# B171B.net
KiCad netlist of a schematic drawn in EAGLE
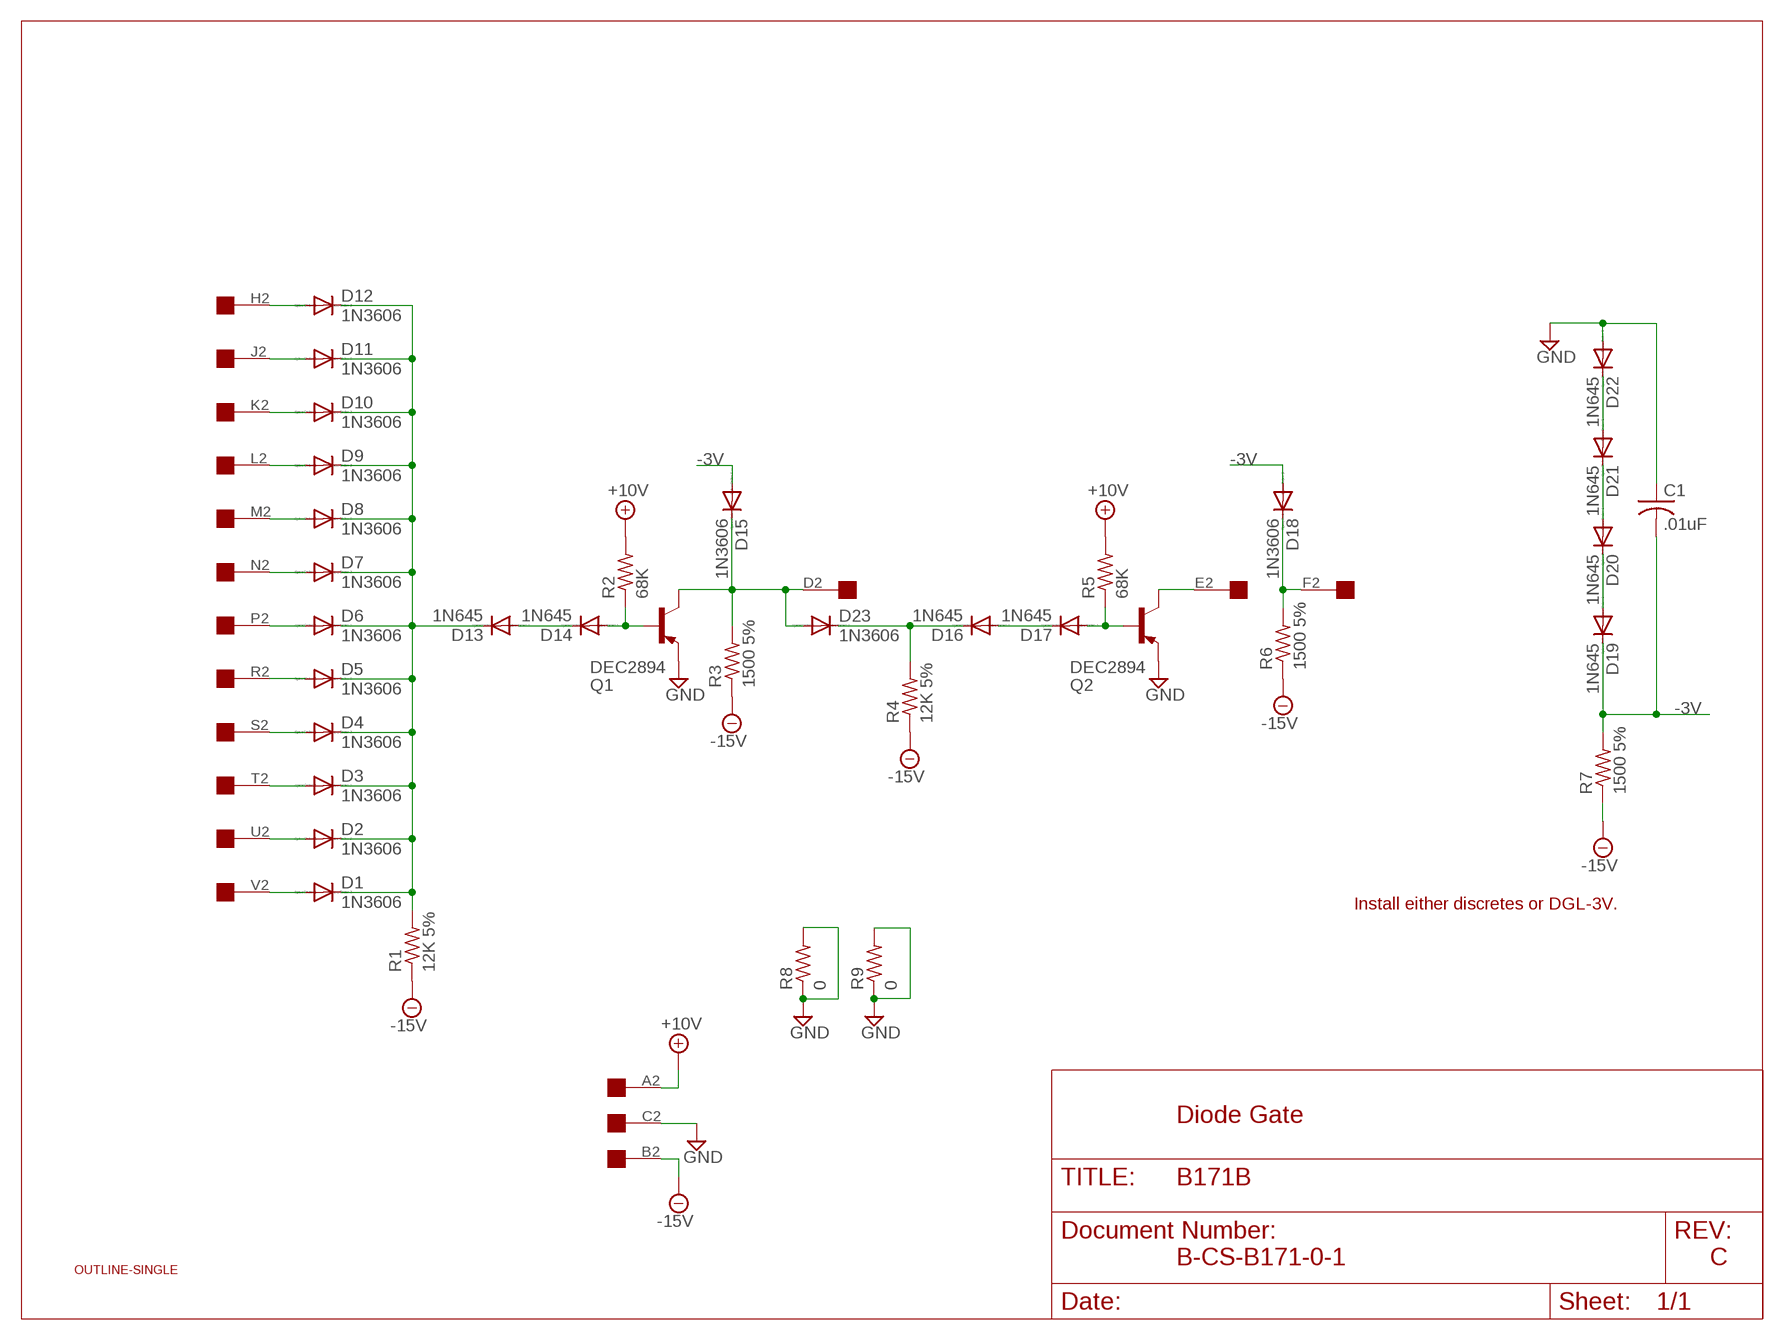
[diagram p0: schematic, sheet 1]

(export (version "E")
  (design (tool "Eeschema 10.0.6"))
  (components
    (comp (ref "C1")
      (value ".01uF")
      (footprint "eagle-import:C063-025X075")
      (libsource (lib "eagle-import") (part "C-US"))
    )
    (comp (ref "D1")
      (value "1N3606")
      (footprint "eagle-import:DO35-10")
      (libsource (lib "eagle-import") (part "DIODE-DO35-10"))
    )
    (comp (ref "D2")
      (value "1N3606")
      (footprint "eagle-import:DO35-10")
      (libsource (lib "eagle-import") (part "DIODE-DO35-10"))
    )
    (comp (ref "D3")
      (value "1N3606")
      (footprint "eagle-import:DO35-10")
      (libsource (lib "eagle-import") (part "DIODE-DO35-10"))
    )
    (comp (ref "D4")
      (value "1N3606")
      (footprint "eagle-import:DO35-10")
      (libsource (lib "eagle-import") (part "DIODE-DO35-10"))
    )
    (comp (ref "D5")
      (value "1N3606")
      (footprint "eagle-import:DO35-10")
      (libsource (lib "eagle-import") (part "DIODE-DO35-10"))
    )
    (comp (ref "D6")
      (value "1N3606")
      (footprint "eagle-import:DO35-10")
      (libsource (lib "eagle-import") (part "DIODE-DO35-10"))
    )
    (comp (ref "D7")
      (value "1N3606")
      (footprint "eagle-import:DO35-10")
      (libsource (lib "eagle-import") (part "DIODE-DO35-10"))
    )
    (comp (ref "D8")
      (value "1N3606")
      (footprint "eagle-import:DO35-10")
      (libsource (lib "eagle-import") (part "DIODE-DO35-10"))
    )
    (comp (ref "D9")
      (value "1N3606")
      (footprint "eagle-import:DO35-10")
      (libsource (lib "eagle-import") (part "DIODE-DO35-10"))
    )
    (comp (ref "D10")
      (value "1N3606")
      (footprint "eagle-import:DO35-10")
      (libsource (lib "eagle-import") (part "DIODE-DO35-10"))
    )
    (comp (ref "D11")
      (value "1N3606")
      (footprint "eagle-import:DO35-10")
      (libsource (lib "eagle-import") (part "DIODE-DO35-10"))
    )
    (comp (ref "D12")
      (value "1N3606")
      (footprint "eagle-import:DO35-10")
      (libsource (lib "eagle-import") (part "DIODE-DO35-10"))
    )
    (comp (ref "D13")
      (value "1N645")
      (footprint "eagle-import:DO35-10")
      (libsource (lib "eagle-import") (part "DIODE-DO35-10"))
    )
    (comp (ref "D14")
      (value "1N645")
      (footprint "eagle-import:DO35-10")
      (libsource (lib "eagle-import") (part "DIODE-DO35-10"))
    )
    (comp (ref "D15")
      (value "1N3606")
      (footprint "eagle-import:DO35-10")
      (libsource (lib "eagle-import") (part "DIODE-DO35-10"))
    )
    (comp (ref "D16")
      (value "1N645")
      (footprint "eagle-import:DO35-10")
      (libsource (lib "eagle-import") (part "DIODE-DO35-10"))
    )
    (comp (ref "D17")
      (value "1N645")
      (footprint "eagle-import:DO35-10")
      (libsource (lib "eagle-import") (part "DIODE-DO35-10"))
    )
    (comp (ref "D18")
      (value "1N3606")
      (footprint "eagle-import:DO35-10")
      (libsource (lib "eagle-import") (part "DIODE-DO35-10"))
    )
    (comp (ref "D19")
      (value "1N645")
      (footprint "eagle-import:DO35-10")
      (libsource (lib "eagle-import") (part "DIODE-DO35-10"))
    )
    (comp (ref "D20")
      (value "1N645")
      (footprint "eagle-import:DO35-10")
      (libsource (lib "eagle-import") (part "DIODE-DO35-10"))
    )
    (comp (ref "D21")
      (value "1N645")
      (footprint "eagle-import:DO35-10")
      (libsource (lib "eagle-import") (part "DIODE-DO35-10"))
    )
    (comp (ref "D22")
      (value "1N645")
      (footprint "eagle-import:DO35-10")
      (libsource (lib "eagle-import") (part "DIODE-DO35-10"))
    )
    (comp (ref "D23")
      (value "1N3606")
      (footprint "eagle-import:DO35-10")
      (libsource (lib "eagle-import") (part "DIODE-DO35-10"))
    )
    (comp (ref "Q1")
      (value "DEC2894")
      (footprint "eagle-import:TO5")
      (libsource (lib "eagle-import") (part "-PNP-TO5"))
    )
    (comp (ref "Q2")
      (value "DEC2894")
      (footprint "eagle-import:TO5")
      (libsource (lib "eagle-import") (part "-PNP-TO5"))
    )
    (comp (ref "R1")
      (value "12K 5%")
      (footprint "eagle-import:0207_10")
      (libsource (lib "eagle-import") (part "R-US_0207/10"))
    )
    (comp (ref "R2")
      (value "68K")
      (footprint "eagle-import:0207_10")
      (libsource (lib "eagle-import") (part "R-US_0207/10"))
    )
    (comp (ref "R3")
      (value "1500 5%")
      (footprint "eagle-import:0207_10")
      (libsource (lib "eagle-import") (part "R-US_0207/10"))
    )
    (comp (ref "R4")
      (value "12K 5%")
      (footprint "eagle-import:0207_10")
      (libsource (lib "eagle-import") (part "R-US_0207/10"))
    )
    (comp (ref "R5")
      (value "68K")
      (footprint "eagle-import:0207_10")
      (libsource (lib "eagle-import") (part "R-US_0207/10"))
    )
    (comp (ref "R6")
      (value "1500 5%")
      (footprint "eagle-import:0207_10")
      (libsource (lib "eagle-import") (part "R-US_0207/10"))
    )
    (comp (ref "R7")
      (value "1500 5%")
      (footprint "eagle-import:0207_10")
      (libsource (lib "eagle-import") (part "R-US_0207/10"))
    )
    (comp (ref "R8")
      (value "0")
      (footprint "eagle-import:0207_10")
      (libsource (lib "eagle-import") (part "R-US_0207/10"))
    )
    (comp (ref "R9")
      (value "0")
      (footprint "eagle-import:0207_10")
      (libsource (lib "eagle-import") (part "R-US_0207/10"))
    )
    (comp (ref "U$1")
      (value "OUTLINE-SINGLE")
      (footprint "eagle-import:SINGLE")
      (libsource (lib "eagle-import") (part "OUTLINE-SINGLE"))
    )
    (comp (ref "U$2")
      (value "EDGE-1")
      (footprint "eagle-import:EDGE-CON1")
      (libsource (lib "eagle-import") (part "EDGE-1"))
    )
  )
  (nets
    (net (code "1") (name "+10V") (class "Default")
      (node (ref "R2") (pin "2") (pinfunction "2_2") (pintype "passive"))
      (node (ref "R5") (pin "2") (pinfunction "2_2") (pintype "passive"))
      (node (ref "U$2") (pin "A2") (pinfunction "1_A2") (pintype "bidirectional"))
    )
    (net (code "2") (name "-15V") (class "Default")
      (node (ref "R1") (pin "1") (pinfunction "1_1") (pintype "passive"))
      (node (ref "R3") (pin "1") (pinfunction "1_1") (pintype "passive"))
      (node (ref "R4") (pin "1") (pinfunction "1_1") (pintype "passive"))
      (node (ref "R6") (pin "1") (pinfunction "1_1") (pintype "passive"))
      (node (ref "R7") (pin "1") (pinfunction "1_1") (pintype "passive"))
      (node (ref "U$2") (pin "B2") (pinfunction "1_B2") (pintype "bidirectional"))
    )
    (net (code "3") (name "/-3V") (class "Default")
      (node (ref "C1") (pin "2") (pinfunction "2_2") (pintype "passive"))
      (node (ref "D15") (pin "A") (pinfunction "A_A") (pintype "passive"))
      (node (ref "D18") (pin "A") (pinfunction "A_A") (pintype "passive"))
      (node (ref "D19") (pin "C") (pinfunction "C_C") (pintype "passive"))
      (node (ref "R7") (pin "2") (pinfunction "2_2") (pintype "passive"))
    )
    (net (code "4") (name "GND") (class "Default")
      (node (ref "C1") (pin "1") (pinfunction "1_1") (pintype "passive"))
      (node (ref "D22") (pin "A") (pinfunction "A_A") (pintype "passive"))
      (node (ref "Q1") (pin "1") (pinfunction "E_1") (pintype "passive"))
      (node (ref "Q2") (pin "1") (pinfunction "E_1") (pintype "passive"))
      (node (ref "R8") (pin "1") (pinfunction "1_1") (pintype "passive"))
      (node (ref "R8") (pin "2") (pinfunction "2_2") (pintype "passive"))
      (node (ref "R9") (pin "1") (pinfunction "1_1") (pintype "passive"))
      (node (ref "R9") (pin "2") (pinfunction "2_2") (pintype "passive"))
      (node (ref "U$2") (pin "C2") (pinfunction "1_C2") (pintype "bidirectional"))
    )
    (net (code "5") (name "Net-(D1-PadC)") (class "Default")
      (node (ref "D1") (pin "C") (pinfunction "C_C") (pintype "passive"))
      (node (ref "D10") (pin "C") (pinfunction "C_C") (pintype "passive"))
      (node (ref "D11") (pin "C") (pinfunction "C_C") (pintype "passive"))
      (node (ref "D12") (pin "C") (pinfunction "C_C") (pintype "passive"))
      (node (ref "D13") (pin "C") (pinfunction "C_C") (pintype "passive"))
      (node (ref "D2") (pin "C") (pinfunction "C_C") (pintype "passive"))
      (node (ref "D3") (pin "C") (pinfunction "C_C") (pintype "passive"))
      (node (ref "D4") (pin "C") (pinfunction "C_C") (pintype "passive"))
      (node (ref "D5") (pin "C") (pinfunction "C_C") (pintype "passive"))
      (node (ref "D6") (pin "C") (pinfunction "C_C") (pintype "passive"))
      (node (ref "D7") (pin "C") (pinfunction "C_C") (pintype "passive"))
      (node (ref "D8") (pin "C") (pinfunction "C_C") (pintype "passive"))
      (node (ref "D9") (pin "C") (pinfunction "C_C") (pintype "passive"))
      (node (ref "R1") (pin "2") (pinfunction "2_2") (pintype "passive"))
    )
    (net (code "6") (name "Net-(D13-PadA)") (class "Default")
      (node (ref "D13") (pin "A") (pinfunction "A_A") (pintype "passive"))
      (node (ref "D14") (pin "C") (pinfunction "C_C") (pintype "passive"))
    )
    (net (code "7") (name "Net-(D16-PadA)") (class "Default")
      (node (ref "D16") (pin "A") (pinfunction "A_A") (pintype "passive"))
      (node (ref "D17") (pin "C") (pinfunction "C_C") (pintype "passive"))
    )
    (net (code "8") (name "Net-(D16-PadC)") (class "Default")
      (node (ref "D16") (pin "C") (pinfunction "C_C") (pintype "passive"))
      (node (ref "D23") (pin "C") (pinfunction "C_C") (pintype "passive"))
      (node (ref "R4") (pin "2") (pinfunction "2_2") (pintype "passive"))
    )
    (net (code "9") (name "Net-(D19-PadA)") (class "Default")
      (node (ref "D19") (pin "A") (pinfunction "A_A") (pintype "passive"))
      (node (ref "D20") (pin "C") (pinfunction "C_C") (pintype "passive"))
    )
    (net (code "10") (name "Net-(D20-PadA)") (class "Default")
      (node (ref "D20") (pin "A") (pinfunction "A_A") (pintype "passive"))
      (node (ref "D21") (pin "C") (pinfunction "C_C") (pintype "passive"))
    )
    (net (code "11") (name "Net-(D21-PadA)") (class "Default")
      (node (ref "D21") (pin "A") (pinfunction "A_A") (pintype "passive"))
      (node (ref "D22") (pin "C") (pinfunction "C_C") (pintype "passive"))
    )
    (net (code "12") (name "Net-(Q1-B)") (class "Default")
      (node (ref "D14") (pin "A") (pinfunction "A_A") (pintype "passive"))
      (node (ref "Q1") (pin "2") (pinfunction "B_2") (pintype "passive"))
      (node (ref "R2") (pin "1") (pinfunction "1_1") (pintype "passive"))
    )
    (net (code "13") (name "Net-(Q1-C)") (class "Default")
      (node (ref "D15") (pin "C") (pinfunction "C_C") (pintype "passive"))
      (node (ref "D23") (pin "A") (pinfunction "A_A") (pintype "passive"))
      (node (ref "Q1") (pin "3") (pinfunction "C_3") (pintype "passive"))
      (node (ref "R3") (pin "2") (pinfunction "2_2") (pintype "passive"))
      (node (ref "U$2") (pin "D2") (pinfunction "1_D2") (pintype "bidirectional"))
    )
    (net (code "14") (name "Net-(Q2-B)") (class "Default")
      (node (ref "D17") (pin "A") (pinfunction "A_A") (pintype "passive"))
      (node (ref "Q2") (pin "2") (pinfunction "B_2") (pintype "passive"))
      (node (ref "R5") (pin "1") (pinfunction "1_1") (pintype "passive"))
    )
    (net (code "15") (name "Net-(Q2-C)") (class "Default")
      (node (ref "Q2") (pin "3") (pinfunction "C_3") (pintype "passive"))
      (node (ref "U$2") (pin "E2") (pinfunction "1_E2") (pintype "bidirectional"))
    )
    (net (code "16") (name "Net-(U$2F-1)") (class "Default")
      (node (ref "D18") (pin "C") (pinfunction "C_C") (pintype "passive"))
      (node (ref "R6") (pin "2") (pinfunction "2_2") (pintype "passive"))
      (node (ref "U$2") (pin "F2") (pinfunction "1_F2") (pintype "bidirectional"))
    )
    (net (code "17") (name "Net-(U$2G-1)") (class "Default")
      (node (ref "D12") (pin "A") (pinfunction "A_A") (pintype "passive"))
      (node (ref "U$2") (pin "H2") (pinfunction "1_H2") (pintype "bidirectional"))
    )
    (net (code "18") (name "Net-(U$2H-1)") (class "Default")
      (node (ref "D11") (pin "A") (pinfunction "A_A") (pintype "passive"))
      (node (ref "U$2") (pin "J2") (pinfunction "1_J2") (pintype "bidirectional"))
    )
    (net (code "19") (name "Net-(U$2I-1)") (class "Default")
      (node (ref "D10") (pin "A") (pinfunction "A_A") (pintype "passive"))
      (node (ref "U$2") (pin "K2") (pinfunction "1_K2") (pintype "bidirectional"))
    )
    (net (code "20") (name "Net-(U$2J-1)") (class "Default")
      (node (ref "D9") (pin "A") (pinfunction "A_A") (pintype "passive"))
      (node (ref "U$2") (pin "L2") (pinfunction "1_L2") (pintype "bidirectional"))
    )
    (net (code "21") (name "Net-(U$2K-1)") (class "Default")
      (node (ref "D8") (pin "A") (pinfunction "A_A") (pintype "passive"))
      (node (ref "U$2") (pin "M2") (pinfunction "1_M2") (pintype "bidirectional"))
    )
    (net (code "22") (name "Net-(U$2L-1)") (class "Default")
      (node (ref "D7") (pin "A") (pinfunction "A_A") (pintype "passive"))
      (node (ref "U$2") (pin "N2") (pinfunction "1_N2") (pintype "bidirectional"))
    )
    (net (code "23") (name "Net-(U$2M-1)") (class "Default")
      (node (ref "D6") (pin "A") (pinfunction "A_A") (pintype "passive"))
      (node (ref "U$2") (pin "P2") (pinfunction "1_P2") (pintype "bidirectional"))
    )
    (net (code "24") (name "Net-(U$2N-1)") (class "Default")
      (node (ref "D5") (pin "A") (pinfunction "A_A") (pintype "passive"))
      (node (ref "U$2") (pin "R2") (pinfunction "1_R2") (pintype "bidirectional"))
    )
    (net (code "25") (name "Net-(U$2O-1)") (class "Default")
      (node (ref "D4") (pin "A") (pinfunction "A_A") (pintype "passive"))
      (node (ref "U$2") (pin "S2") (pinfunction "1_S2") (pintype "bidirectional"))
    )
    (net (code "26") (name "Net-(U$2P-1)") (class "Default")
      (node (ref "D3") (pin "A") (pinfunction "A_A") (pintype "passive"))
      (node (ref "U$2") (pin "T2") (pinfunction "1_T2") (pintype "bidirectional"))
    )
    (net (code "27") (name "Net-(U$2Q-1)") (class "Default")
      (node (ref "D2") (pin "A") (pinfunction "A_A") (pintype "passive"))
      (node (ref "U$2") (pin "U2") (pinfunction "1_U2") (pintype "bidirectional"))
    )
    (net (code "28") (name "Net-(U$2R-1)") (class "Default")
      (node (ref "D1") (pin "A") (pinfunction "A_A") (pintype "passive"))
      (node (ref "U$2") (pin "V2") (pinfunction "1_V2") (pintype "bidirectional"))
    )
  )
)
